# DotMatrix8x8.net
KiCad netlist of a schematic drawn in EAGLE
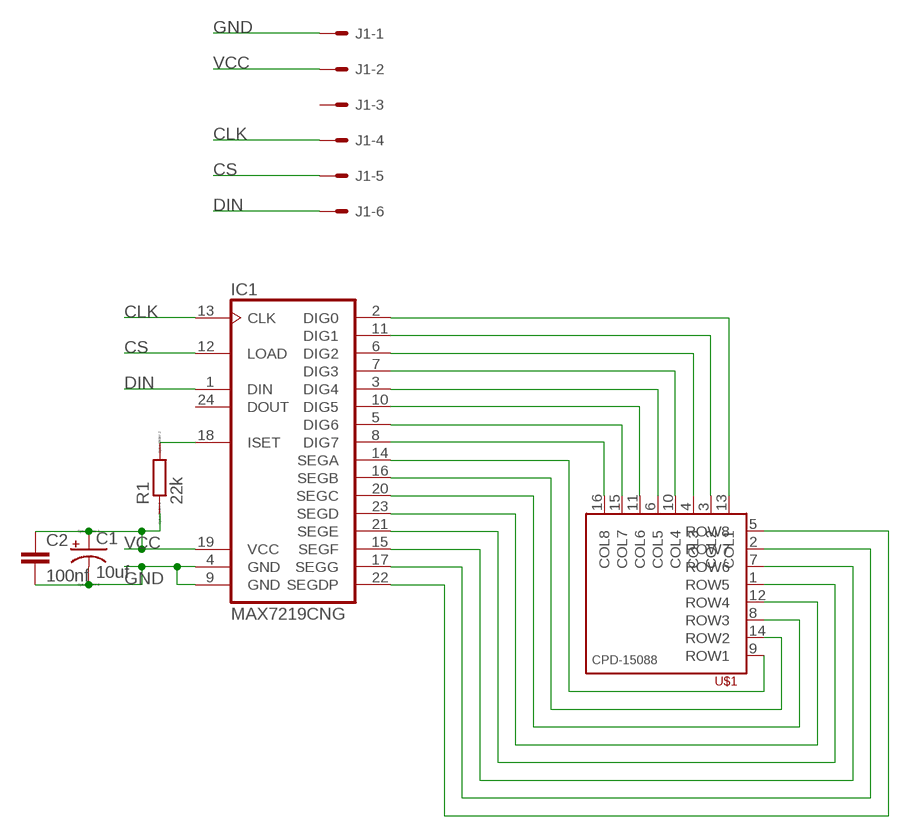
[diagram p0: schematic, sheet 1]

(export (version "E")
  (design (tool "Eeschema 10.0.6"))
  (components
    (comp (ref "C1")
      (value "10uf")
      (footprint "eagle-import:E2,5-6")
      (libsource (lib "eagle-import") (part "CPOL-USE2.5-6"))
    )
    (comp (ref "C2")
      (value "100nf")
      (footprint "eagle-import:C025-025X050")
      (libsource (lib "eagle-import") (part "C-EU025-025X050"))
    )
    (comp (ref "IC1")
      (value "MAX7219CNG")
      (footprint "eagle-import:DIL24-3")
      (fields (field (name "MF") "MAXIM"))
      (libsource (lib "eagle-import") (part "MAX7219CNG"))
    )
    (comp (ref "J1")
      (value "22-27-2061-06")
      (footprint "eagle-import:6410-06")
      (libsource (lib "eagle-import") (part "22-?-0627-2061"))
    )
    (comp (ref "R1")
      (value "22k")
      (footprint "eagle-import:0207_10")
      (libsource (lib "eagle-import") (part "R0207/10"))
    )
    (comp (ref "U$1")
      (value "CPD-15088YGD2/A")
      (footprint "eagle-import:CPD15088")
      (libsource (lib "eagle-import") (part "CPD-15088YGD2/A"))
    )
  )
  (nets
    (net (code "1") (name "/CLK") (class "Default")
      (node (ref "IC1") (pin "13") (pinfunction "CLK_13") (pintype "input"))
      (node (ref "J1") (pin "4") (pinfunction "S_4") (pintype "passive"))
    )
    (net (code "2") (name "/CS") (class "Default")
      (node (ref "IC1") (pin "12") (pinfunction "LOAD_12") (pintype "input"))
      (node (ref "J1") (pin "5") (pinfunction "S_5") (pintype "passive"))
    )
    (net (code "3") (name "/DIN") (class "Default")
      (node (ref "IC1") (pin "1") (pinfunction "DIN_1") (pintype "input"))
      (node (ref "J1") (pin "6") (pinfunction "S_6") (pintype "passive"))
    )
    (net (code "4") (name "/GND") (class "Default")
      (node (ref "C1") (pin "-") (pinfunction "-_-") (pintype "passive"))
      (node (ref "C2") (pin "2") (pinfunction "2_2") (pintype "passive"))
      (node (ref "IC1") (pin "4") (pinfunction "GND_4") (pintype "power_in"))
      (node (ref "IC1") (pin "9") (pinfunction "GND_9") (pintype "power_in"))
      (node (ref "J1") (pin "1") (pinfunction "S_1") (pintype "passive"))
    )
    (net (code "5") (name "/VCC") (class "Default")
      (node (ref "C1") (pin "+") (pinfunction "+_+") (pintype "passive"))
      (node (ref "C2") (pin "1") (pinfunction "1_1") (pintype "passive"))
      (node (ref "IC1") (pin "19") (pinfunction "VCC_19") (pintype "power_in"))
      (node (ref "J1") (pin "2") (pinfunction "S_2") (pintype "passive"))
      (node (ref "R1") (pin "1") (pinfunction "1_1") (pintype "passive"))
    )
    (net (code "6") (name "Net-(IC1-DIG0)") (class "Default")
      (node (ref "IC1") (pin "2") (pinfunction "DIG0_2") (pintype "output"))
      (node (ref "U$1") (pin "13") (pinfunction "COL1_13") (pintype "bidirectional"))
    )
    (net (code "7") (name "Net-(IC1-DIG1)") (class "Default")
      (node (ref "IC1") (pin "11") (pinfunction "DIG1_11") (pintype "output"))
      (node (ref "U$1") (pin "3") (pinfunction "COL2_3") (pintype "bidirectional"))
    )
    (net (code "8") (name "Net-(IC1-DIG2)") (class "Default")
      (node (ref "IC1") (pin "6") (pinfunction "DIG2_6") (pintype "output"))
      (node (ref "U$1") (pin "4") (pinfunction "COL3_4") (pintype "bidirectional"))
    )
    (net (code "9") (name "Net-(IC1-DIG3)") (class "Default")
      (node (ref "IC1") (pin "7") (pinfunction "DIG3_7") (pintype "output"))
      (node (ref "U$1") (pin "10") (pinfunction "COL4_10") (pintype "bidirectional"))
    )
    (net (code "10") (name "Net-(IC1-DIG4)") (class "Default")
      (node (ref "IC1") (pin "3") (pinfunction "DIG4_3") (pintype "output"))
      (node (ref "U$1") (pin "6") (pinfunction "COL5_6") (pintype "bidirectional"))
    )
    (net (code "11") (name "Net-(IC1-DIG5)") (class "Default")
      (node (ref "IC1") (pin "10") (pinfunction "DIG5_10") (pintype "output"))
      (node (ref "U$1") (pin "11") (pinfunction "COL6_11") (pintype "bidirectional"))
    )
    (net (code "12") (name "Net-(IC1-DIG6)") (class "Default")
      (node (ref "IC1") (pin "5") (pinfunction "DIG6_5") (pintype "output"))
      (node (ref "U$1") (pin "15") (pinfunction "COL7_15") (pintype "bidirectional"))
    )
    (net (code "13") (name "Net-(IC1-DIG7)") (class "Default")
      (node (ref "IC1") (pin "8") (pinfunction "DIG7_8") (pintype "output"))
      (node (ref "U$1") (pin "16") (pinfunction "COL8_16") (pintype "bidirectional"))
    )
    (net (code "14") (name "Net-(IC1-ISET)") (class "Default")
      (node (ref "IC1") (pin "18") (pinfunction "ISET_18") (pintype "input"))
      (node (ref "R1") (pin "2") (pinfunction "2_2") (pintype "passive"))
    )
    (net (code "15") (name "Net-(IC1-SEGA)") (class "Default")
      (node (ref "IC1") (pin "14") (pinfunction "SEGA_14") (pintype "output"))
      (node (ref "U$1") (pin "9") (pinfunction "ROW1_9") (pintype "bidirectional"))
    )
    (net (code "16") (name "Net-(IC1-SEGB)") (class "Default")
      (node (ref "IC1") (pin "16") (pinfunction "SEGB_16") (pintype "output"))
      (node (ref "U$1") (pin "14") (pinfunction "ROW2_14") (pintype "bidirectional"))
    )
    (net (code "17") (name "Net-(IC1-SEGC)") (class "Default")
      (node (ref "IC1") (pin "20") (pinfunction "SEGC_20") (pintype "output"))
      (node (ref "U$1") (pin "8") (pinfunction "ROW3_8") (pintype "bidirectional"))
    )
    (net (code "18") (name "Net-(IC1-SEGD)") (class "Default")
      (node (ref "IC1") (pin "23") (pinfunction "SEGD_23") (pintype "output"))
      (node (ref "U$1") (pin "12") (pinfunction "ROW4_12") (pintype "bidirectional"))
    )
    (net (code "19") (name "Net-(IC1-SEGDP)") (class "Default")
      (node (ref "IC1") (pin "22") (pinfunction "SEGDP_22") (pintype "output"))
      (node (ref "U$1") (pin "5") (pinfunction "ROW8_5") (pintype "bidirectional"))
    )
    (net (code "20") (name "Net-(IC1-SEGE)") (class "Default")
      (node (ref "IC1") (pin "21") (pinfunction "SEGE_21") (pintype "output"))
      (node (ref "U$1") (pin "1") (pinfunction "ROW5_1") (pintype "bidirectional"))
    )
    (net (code "21") (name "Net-(IC1-SEGF)") (class "Default")
      (node (ref "IC1") (pin "15") (pinfunction "SEGF_15") (pintype "output"))
      (node (ref "U$1") (pin "7") (pinfunction "ROW6_7") (pintype "bidirectional"))
    )
    (net (code "22") (name "Net-(IC1-SEGG)") (class "Default")
      (node (ref "IC1") (pin "17") (pinfunction "SEGG_17") (pintype "output"))
      (node (ref "U$1") (pin "2") (pinfunction "ROW7_2") (pintype "bidirectional"))
    )
    (net (code "23") (name "unconnected-(IC1-DOUT-Pad24)") (class "Default")
      (node (ref "IC1") (pin "24") (pinfunction "DOUT_24") (pintype "output"))
    )
    (net (code "24") (name "unconnected-(J1C-S-Pad3)") (class "Default")
      (node (ref "J1") (pin "3") (pinfunction "S_3") (pintype "passive"))
    )
  )
)
